# TapDriver.net
KiCad netlist of a schematic drawn in Altium Designer
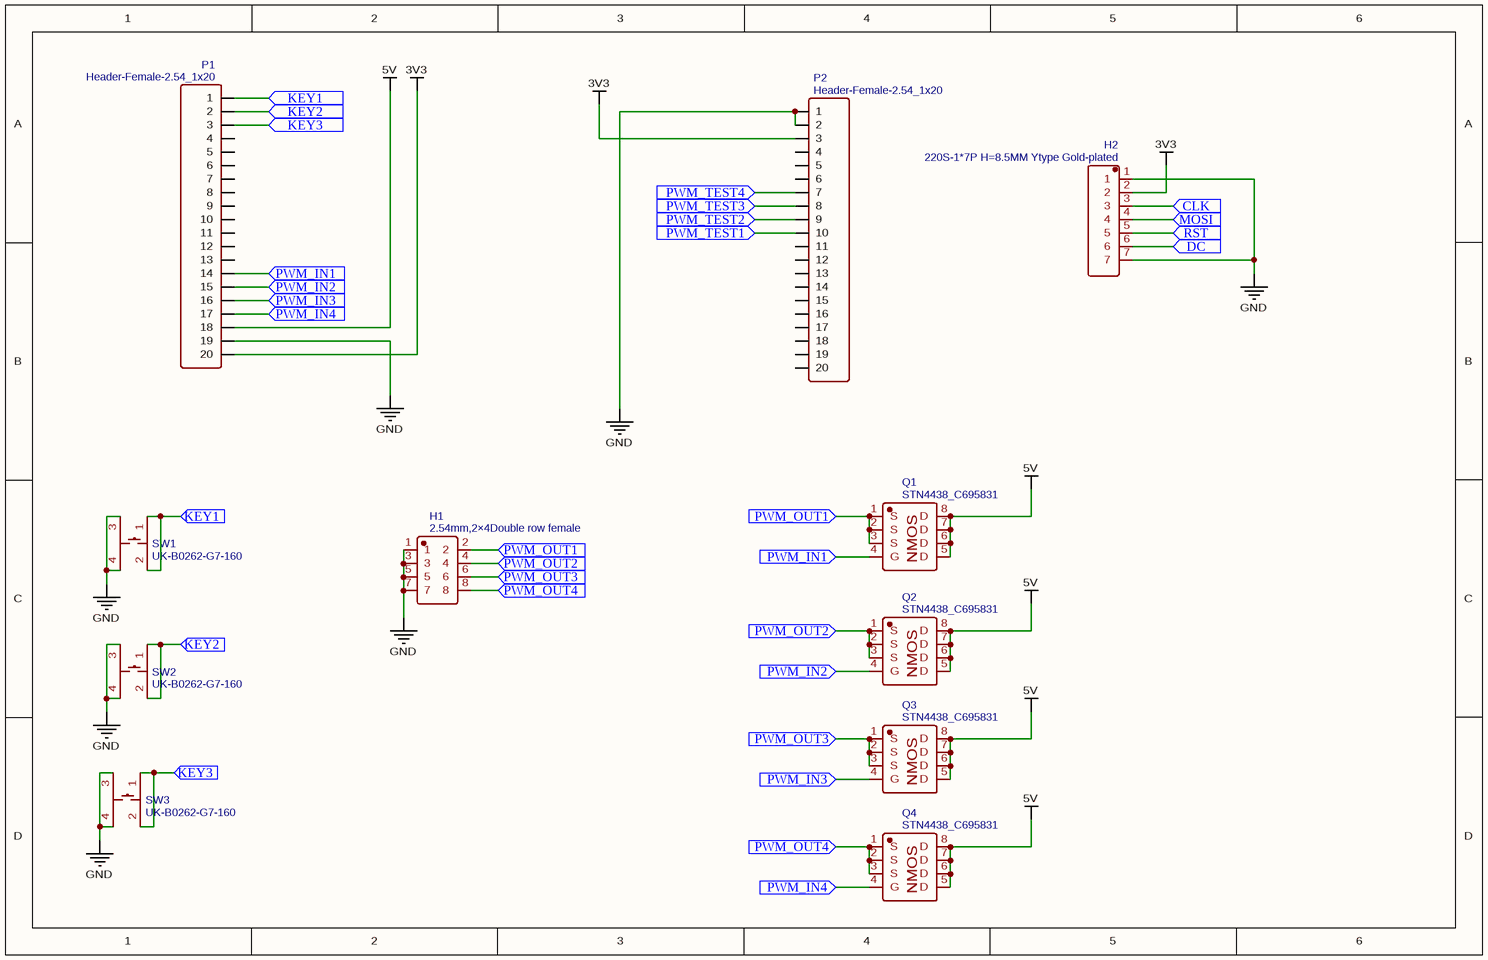
[diagram p0: TapDriver.schdoc]

(export (version "E")
  (design (tool "Eeschema 10.0.6"))
  (components
    (comp (ref "H1")
      (value "2.54mm,2×4Double row female")
      (footprint "HDR-TH_8P-P2.54-V-F-R2-C4-S2.54-1")
      (fields (field (name "BOM_SUPPLIER PART") "C58378"))
      (libsource (lib "altium-import") (part "root_0_2.54mm,2×4Double row female_"))
    )
    (comp (ref "H2")
      (value "220S-1*7P H=8.5MM Ytype Gold-plated")
      (footprint "HDR-TH_7P-P2.54-V-F")
      (fields (field (name "BOM_SUPPLIER PART") "C124418") (field (name "CONTRIBUTOR") "LCSC"))
      (libsource (lib "altium-import") (part "root_0_220S-1*7P H=8.5MM Ytype Gold-plated_"))
    )
    (comp (ref "P1")
      (value "Header-Female-2.54_1x20")
      (footprint "HDR-TH_20P-P2.54-V-F")
      (fields
        (field (name "BOM_MANUFACTURER PART") "2.54mm 1*20P Female header")
        (field (name "BOM_SUPPLIER PART") "C50984")
      )
      (libsource (lib "") (part "root_0_Header-Female-2.54_1x20__1"))
    )
    (comp (ref "P2")
      (value "Header-Female-2.54_1x20")
      (footprint "HDR-TH_20P-P2.54-V-F")
      (fields
        (field (name "BOM_MANUFACTURER PART") "2.54mm 1*20P Female header")
        (field (name "BOM_SUPPLIER PART") "C50984")
      )
      (libsource (lib "altium-import") (part "root_0_Header-Female-2.54_1x20_"))
    )
    (comp (ref "Q1")
      (value "STN4438_C695831")
      (footprint "SOP-8_L4.9-W3.9-P1.27-LS6.0-BL")
      (fields
        (field (name "BOM_SUPPLIER PART") "C695831")
        (field (name "BOM_MANUFACTURER PART") "STN4438")
        (field (name "CONTRIBUTOR") "LCSC")
      )
      (libsource (lib "altium-import") (part "root_0_STN4438_C695831_"))
    )
    (comp (ref "Q2")
      (value "STN4438_C695831")
      (footprint "SOP-8_L4.9-W3.9-P1.27-LS6.0-BL")
      (fields
        (field (name "BOM_SUPPLIER PART") "C695831")
        (field (name "BOM_MANUFACTURER PART") "STN4438")
        (field (name "CONTRIBUTOR") "LCSC")
      )
      (libsource (lib "altium-import") (part "root_0_STN4438_C695831_"))
    )
    (comp (ref "Q3")
      (value "STN4438_C695831")
      (footprint "SOP-8_L4.9-W3.9-P1.27-LS6.0-BL")
      (fields
        (field (name "BOM_SUPPLIER PART") "C695831")
        (field (name "BOM_MANUFACTURER PART") "STN4438")
        (field (name "CONTRIBUTOR") "LCSC")
      )
      (libsource (lib "altium-import") (part "root_0_STN4438_C695831_"))
    )
    (comp (ref "Q4")
      (value "STN4438_C695831")
      (footprint "SOP-8_L4.9-W3.9-P1.27-LS6.0-BL")
      (fields
        (field (name "BOM_SUPPLIER PART") "C695831")
        (field (name "BOM_MANUFACTURER PART") "STN4438")
        (field (name "CONTRIBUTOR") "LCSC")
      )
      (libsource (lib "altium-import") (part "root_0_STN4438_C695831_"))
    )
    (comp (ref "SW1")
      (value "UK-B0262-G7-160")
      (footprint "SW-SMD_4P-L12.0-W12.0-P5.00-LS15.0")
      (fields (field (name "BOM_SUPPLIER PART") "C620352") (field (name "CONTRIBUTOR") "LCSC"))
      (libsource (lib "altium-import") (part "root_3_UK-B0262-G7-160_"))
    )
    (comp (ref "SW2")
      (value "UK-B0262-G7-160")
      (footprint "SW-SMD_4P-L12.0-W12.0-P5.00-LS15.0")
      (fields (field (name "BOM_SUPPLIER PART") "C620352") (field (name "CONTRIBUTOR") "LCSC"))
      (libsource (lib "altium-import") (part "root_3_UK-B0262-G7-160_"))
    )
    (comp (ref "SW3")
      (value "UK-B0262-G7-160")
      (footprint "SW-SMD_4P-L12.0-W12.0-P5.00-LS15.0")
      (fields (field (name "BOM_SUPPLIER PART") "C620352") (field (name "CONTRIBUTOR") "LCSC"))
      (libsource (lib "altium-import") (part "root_3_UK-B0262-G7-160_"))
    )
  )
  (nets
    (net (code "1") (name "/CLK") (class "Default")
      (node (ref "H2") (pin "3") (pinfunction "3_3") (pintype "passive"))
    )
    (net (code "2") (name "/DC") (class "Default")
      (node (ref "H2") (pin "6") (pinfunction "6_6") (pintype "passive"))
    )
    (net (code "3") (name "/KEY1") (class "Default")
      (node (ref "P1") (pin "1") (pinfunction "1_1") (pintype "passive"))
      (node (ref "SW1") (pin "1") (pinfunction "1_1") (pintype "passive"))
      (node (ref "SW1") (pin "2") (pinfunction "2_2") (pintype "passive"))
    )
    (net (code "4") (name "/KEY2") (class "Default")
      (node (ref "P1") (pin "2") (pinfunction "2_2") (pintype "passive"))
      (node (ref "SW2") (pin "1") (pinfunction "1_1") (pintype "passive"))
      (node (ref "SW2") (pin "2") (pinfunction "2_2") (pintype "passive"))
    )
    (net (code "5") (name "/KEY3") (class "Default")
      (node (ref "P1") (pin "3") (pinfunction "3_3") (pintype "passive"))
      (node (ref "SW3") (pin "1") (pinfunction "1_1") (pintype "passive"))
      (node (ref "SW3") (pin "2") (pinfunction "2_2") (pintype "passive"))
    )
    (net (code "6") (name "/MOSI") (class "Default")
      (node (ref "H2") (pin "4") (pinfunction "4_4") (pintype "passive"))
    )
    (net (code "7") (name "/PWM_IN1") (class "Default")
      (node (ref "P1") (pin "14") (pinfunction "14_14") (pintype "passive"))
      (node (ref "Q1") (pin "4") (pinfunction "G_4") (pintype "passive"))
    )
    (net (code "8") (name "/PWM_IN2") (class "Default")
      (node (ref "P1") (pin "15") (pinfunction "15_15") (pintype "passive"))
      (node (ref "Q2") (pin "4") (pinfunction "G_4") (pintype "passive"))
    )
    (net (code "9") (name "/PWM_IN3") (class "Default")
      (node (ref "P1") (pin "16") (pinfunction "16_16") (pintype "passive"))
      (node (ref "Q3") (pin "4") (pinfunction "G_4") (pintype "passive"))
    )
    (net (code "10") (name "/PWM_IN4") (class "Default")
      (node (ref "P1") (pin "17") (pinfunction "17_17") (pintype "passive"))
      (node (ref "Q4") (pin "4") (pinfunction "G_4") (pintype "passive"))
    )
    (net (code "11") (name "/PWM_OUT1") (class "Default")
      (node (ref "H1") (pin "2") (pinfunction "2_2") (pintype "passive"))
      (node (ref "Q1") (pin "1") (pinfunction "S_1") (pintype "passive"))
      (node (ref "Q1") (pin "2") (pinfunction "S_2") (pintype "passive"))
      (node (ref "Q1") (pin "3") (pinfunction "S_3") (pintype "passive"))
    )
    (net (code "12") (name "/PWM_OUT2") (class "Default")
      (node (ref "H1") (pin "4") (pinfunction "4_4") (pintype "passive"))
      (node (ref "Q2") (pin "1") (pinfunction "S_1") (pintype "passive"))
      (node (ref "Q2") (pin "2") (pinfunction "S_2") (pintype "passive"))
      (node (ref "Q2") (pin "3") (pinfunction "S_3") (pintype "passive"))
    )
    (net (code "13") (name "/PWM_OUT3") (class "Default")
      (node (ref "H1") (pin "6") (pinfunction "6_6") (pintype "passive"))
      (node (ref "Q3") (pin "1") (pinfunction "S_1") (pintype "passive"))
      (node (ref "Q3") (pin "2") (pinfunction "S_2") (pintype "passive"))
      (node (ref "Q3") (pin "3") (pinfunction "S_3") (pintype "passive"))
    )
    (net (code "14") (name "/PWM_OUT4") (class "Default")
      (node (ref "H1") (pin "8") (pinfunction "8_8") (pintype "passive"))
      (node (ref "Q4") (pin "1") (pinfunction "S_1") (pintype "passive"))
      (node (ref "Q4") (pin "2") (pinfunction "S_2") (pintype "passive"))
      (node (ref "Q4") (pin "3") (pinfunction "S_3") (pintype "passive"))
    )
    (net (code "15") (name "/PWM_TEST1") (class "Default")
      (node (ref "P2") (pin "10") (pinfunction "10_10") (pintype "passive"))
    )
    (net (code "16") (name "/PWM_TEST2") (class "Default")
      (node (ref "P2") (pin "9") (pinfunction "9_9") (pintype "passive"))
    )
    (net (code "17") (name "/PWM_TEST3") (class "Default")
      (node (ref "P2") (pin "8") (pinfunction "8_8") (pintype "passive"))
    )
    (net (code "18") (name "/PWM_TEST4") (class "Default")
      (node (ref "P2") (pin "7") (pinfunction "7_7") (pintype "passive"))
    )
    (net (code "19") (name "/RST") (class "Default")
      (node (ref "H2") (pin "5") (pinfunction "5_5") (pintype "passive"))
    )
    (net (code "20") (name "3V3") (class "Default")
      (node (ref "H2") (pin "2") (pinfunction "2_2") (pintype "passive"))
      (node (ref "P1") (pin "20") (pinfunction "20_20") (pintype "passive"))
      (node (ref "P2") (pin "3") (pinfunction "3_3") (pintype "passive"))
    )
    (net (code "21") (name "5V") (class "Default")
      (node (ref "P1") (pin "18") (pinfunction "18_18") (pintype "passive"))
      (node (ref "Q1") (pin "5") (pinfunction "D_5") (pintype "passive"))
      (node (ref "Q1") (pin "6") (pinfunction "D_6") (pintype "passive"))
      (node (ref "Q1") (pin "7") (pinfunction "D_7") (pintype "passive"))
      (node (ref "Q1") (pin "8") (pinfunction "D_8") (pintype "passive"))
      (node (ref "Q2") (pin "5") (pinfunction "D_5") (pintype "passive"))
      (node (ref "Q2") (pin "6") (pinfunction "D_6") (pintype "passive"))
      (node (ref "Q2") (pin "7") (pinfunction "D_7") (pintype "passive"))
      (node (ref "Q2") (pin "8") (pinfunction "D_8") (pintype "passive"))
      (node (ref "Q3") (pin "5") (pinfunction "D_5") (pintype "passive"))
      (node (ref "Q3") (pin "6") (pinfunction "D_6") (pintype "passive"))
      (node (ref "Q3") (pin "7") (pinfunction "D_7") (pintype "passive"))
      (node (ref "Q3") (pin "8") (pinfunction "D_8") (pintype "passive"))
      (node (ref "Q4") (pin "5") (pinfunction "D_5") (pintype "passive"))
      (node (ref "Q4") (pin "6") (pinfunction "D_6") (pintype "passive"))
      (node (ref "Q4") (pin "7") (pinfunction "D_7") (pintype "passive"))
      (node (ref "Q4") (pin "8") (pinfunction "D_8") (pintype "passive"))
    )
    (net (code "22") (name "GND") (class "Default")
      (node (ref "H1") (pin "1") (pinfunction "1_1") (pintype "passive"))
      (node (ref "H1") (pin "3") (pinfunction "3_3") (pintype "passive"))
      (node (ref "H1") (pin "5") (pinfunction "5_5") (pintype "passive"))
      (node (ref "H1") (pin "7") (pinfunction "7_7") (pintype "passive"))
      (node (ref "H2") (pin "1") (pinfunction "1_1") (pintype "passive"))
      (node (ref "H2") (pin "7") (pinfunction "7_7") (pintype "passive"))
      (node (ref "P1") (pin "19") (pinfunction "19_19") (pintype "passive"))
      (node (ref "P2") (pin "1") (pinfunction "1_1") (pintype "passive"))
      (node (ref "P2") (pin "2") (pinfunction "2_2") (pintype "passive"))
      (node (ref "SW1") (pin "3") (pinfunction "3_3") (pintype "passive"))
      (node (ref "SW1") (pin "4") (pinfunction "4_4") (pintype "passive"))
      (node (ref "SW2") (pin "3") (pinfunction "3_3") (pintype "passive"))
      (node (ref "SW2") (pin "4") (pinfunction "4_4") (pintype "passive"))
      (node (ref "SW3") (pin "3") (pinfunction "3_3") (pintype "passive"))
      (node (ref "SW3") (pin "4") (pinfunction "4_4") (pintype "passive"))
    )
    (net (code "23") (name "unconnected-(P1-Pad4)") (class "Default")
      (node (ref "P1") (pin "4") (pinfunction "4_4") (pintype "passive"))
    )
    (net (code "24") (name "unconnected-(P1-Pad5)") (class "Default")
      (node (ref "P1") (pin "5") (pinfunction "5_5") (pintype "passive"))
    )
    (net (code "25") (name "unconnected-(P1-Pad6)") (class "Default")
      (node (ref "P1") (pin "6") (pinfunction "6_6") (pintype "passive"))
    )
    (net (code "26") (name "unconnected-(P1-Pad7)") (class "Default")
      (node (ref "P1") (pin "7") (pinfunction "7_7") (pintype "passive"))
    )
    (net (code "27") (name "unconnected-(P1-Pad8)") (class "Default")
      (node (ref "P1") (pin "8") (pinfunction "8_8") (pintype "passive"))
    )
    (net (code "28") (name "unconnected-(P1-Pad9)") (class "Default")
      (node (ref "P1") (pin "9") (pinfunction "9_9") (pintype "passive"))
    )
    (net (code "29") (name "unconnected-(P1-Pad10)") (class "Default")
      (node (ref "P1") (pin "10") (pinfunction "10_10") (pintype "passive"))
    )
    (net (code "30") (name "unconnected-(P1-Pad11)") (class "Default")
      (node (ref "P1") (pin "11") (pinfunction "11_11") (pintype "passive"))
    )
    (net (code "31") (name "unconnected-(P1-Pad12)") (class "Default")
      (node (ref "P1") (pin "12") (pinfunction "12_12") (pintype "passive"))
    )
    (net (code "32") (name "unconnected-(P1-Pad13)") (class "Default")
      (node (ref "P1") (pin "13") (pinfunction "13_13") (pintype "passive"))
    )
    (net (code "33") (name "unconnected-(P2-Pad4)") (class "Default")
      (node (ref "P2") (pin "4") (pinfunction "4_4") (pintype "passive"))
    )
    (net (code "34") (name "unconnected-(P2-Pad5)") (class "Default")
      (node (ref "P2") (pin "5") (pinfunction "5_5") (pintype "passive"))
    )
    (net (code "35") (name "unconnected-(P2-Pad6)") (class "Default")
      (node (ref "P2") (pin "6") (pinfunction "6_6") (pintype "passive"))
    )
    (net (code "36") (name "unconnected-(P2-Pad11)") (class "Default")
      (node (ref "P2") (pin "11") (pinfunction "11_11") (pintype "passive"))
    )
    (net (code "37") (name "unconnected-(P2-Pad12)") (class "Default")
      (node (ref "P2") (pin "12") (pinfunction "12_12") (pintype "passive"))
    )
    (net (code "38") (name "unconnected-(P2-Pad13)") (class "Default")
      (node (ref "P2") (pin "13") (pinfunction "13_13") (pintype "passive"))
    )
    (net (code "39") (name "unconnected-(P2-Pad14)") (class "Default")
      (node (ref "P2") (pin "14") (pinfunction "14_14") (pintype "passive"))
    )
    (net (code "40") (name "unconnected-(P2-Pad15)") (class "Default")
      (node (ref "P2") (pin "15") (pinfunction "15_15") (pintype "passive"))
    )
    (net (code "41") (name "unconnected-(P2-Pad16)") (class "Default")
      (node (ref "P2") (pin "16") (pinfunction "16_16") (pintype "passive"))
    )
    (net (code "42") (name "unconnected-(P2-Pad17)") (class "Default")
      (node (ref "P2") (pin "17") (pinfunction "17_17") (pintype "passive"))
    )
    (net (code "43") (name "unconnected-(P2-Pad18)") (class "Default")
      (node (ref "P2") (pin "18") (pinfunction "18_18") (pintype "passive"))
    )
    (net (code "44") (name "unconnected-(P2-Pad19)") (class "Default")
      (node (ref "P2") (pin "19") (pinfunction "19_19") (pintype "passive"))
    )
    (net (code "45") (name "unconnected-(P2-Pad20)") (class "Default")
      (node (ref "P2") (pin "20") (pinfunction "20_20") (pintype "passive"))
    )
  )
)
